# MCU.net
KiCad netlist of a schematic drawn in Altium Designer
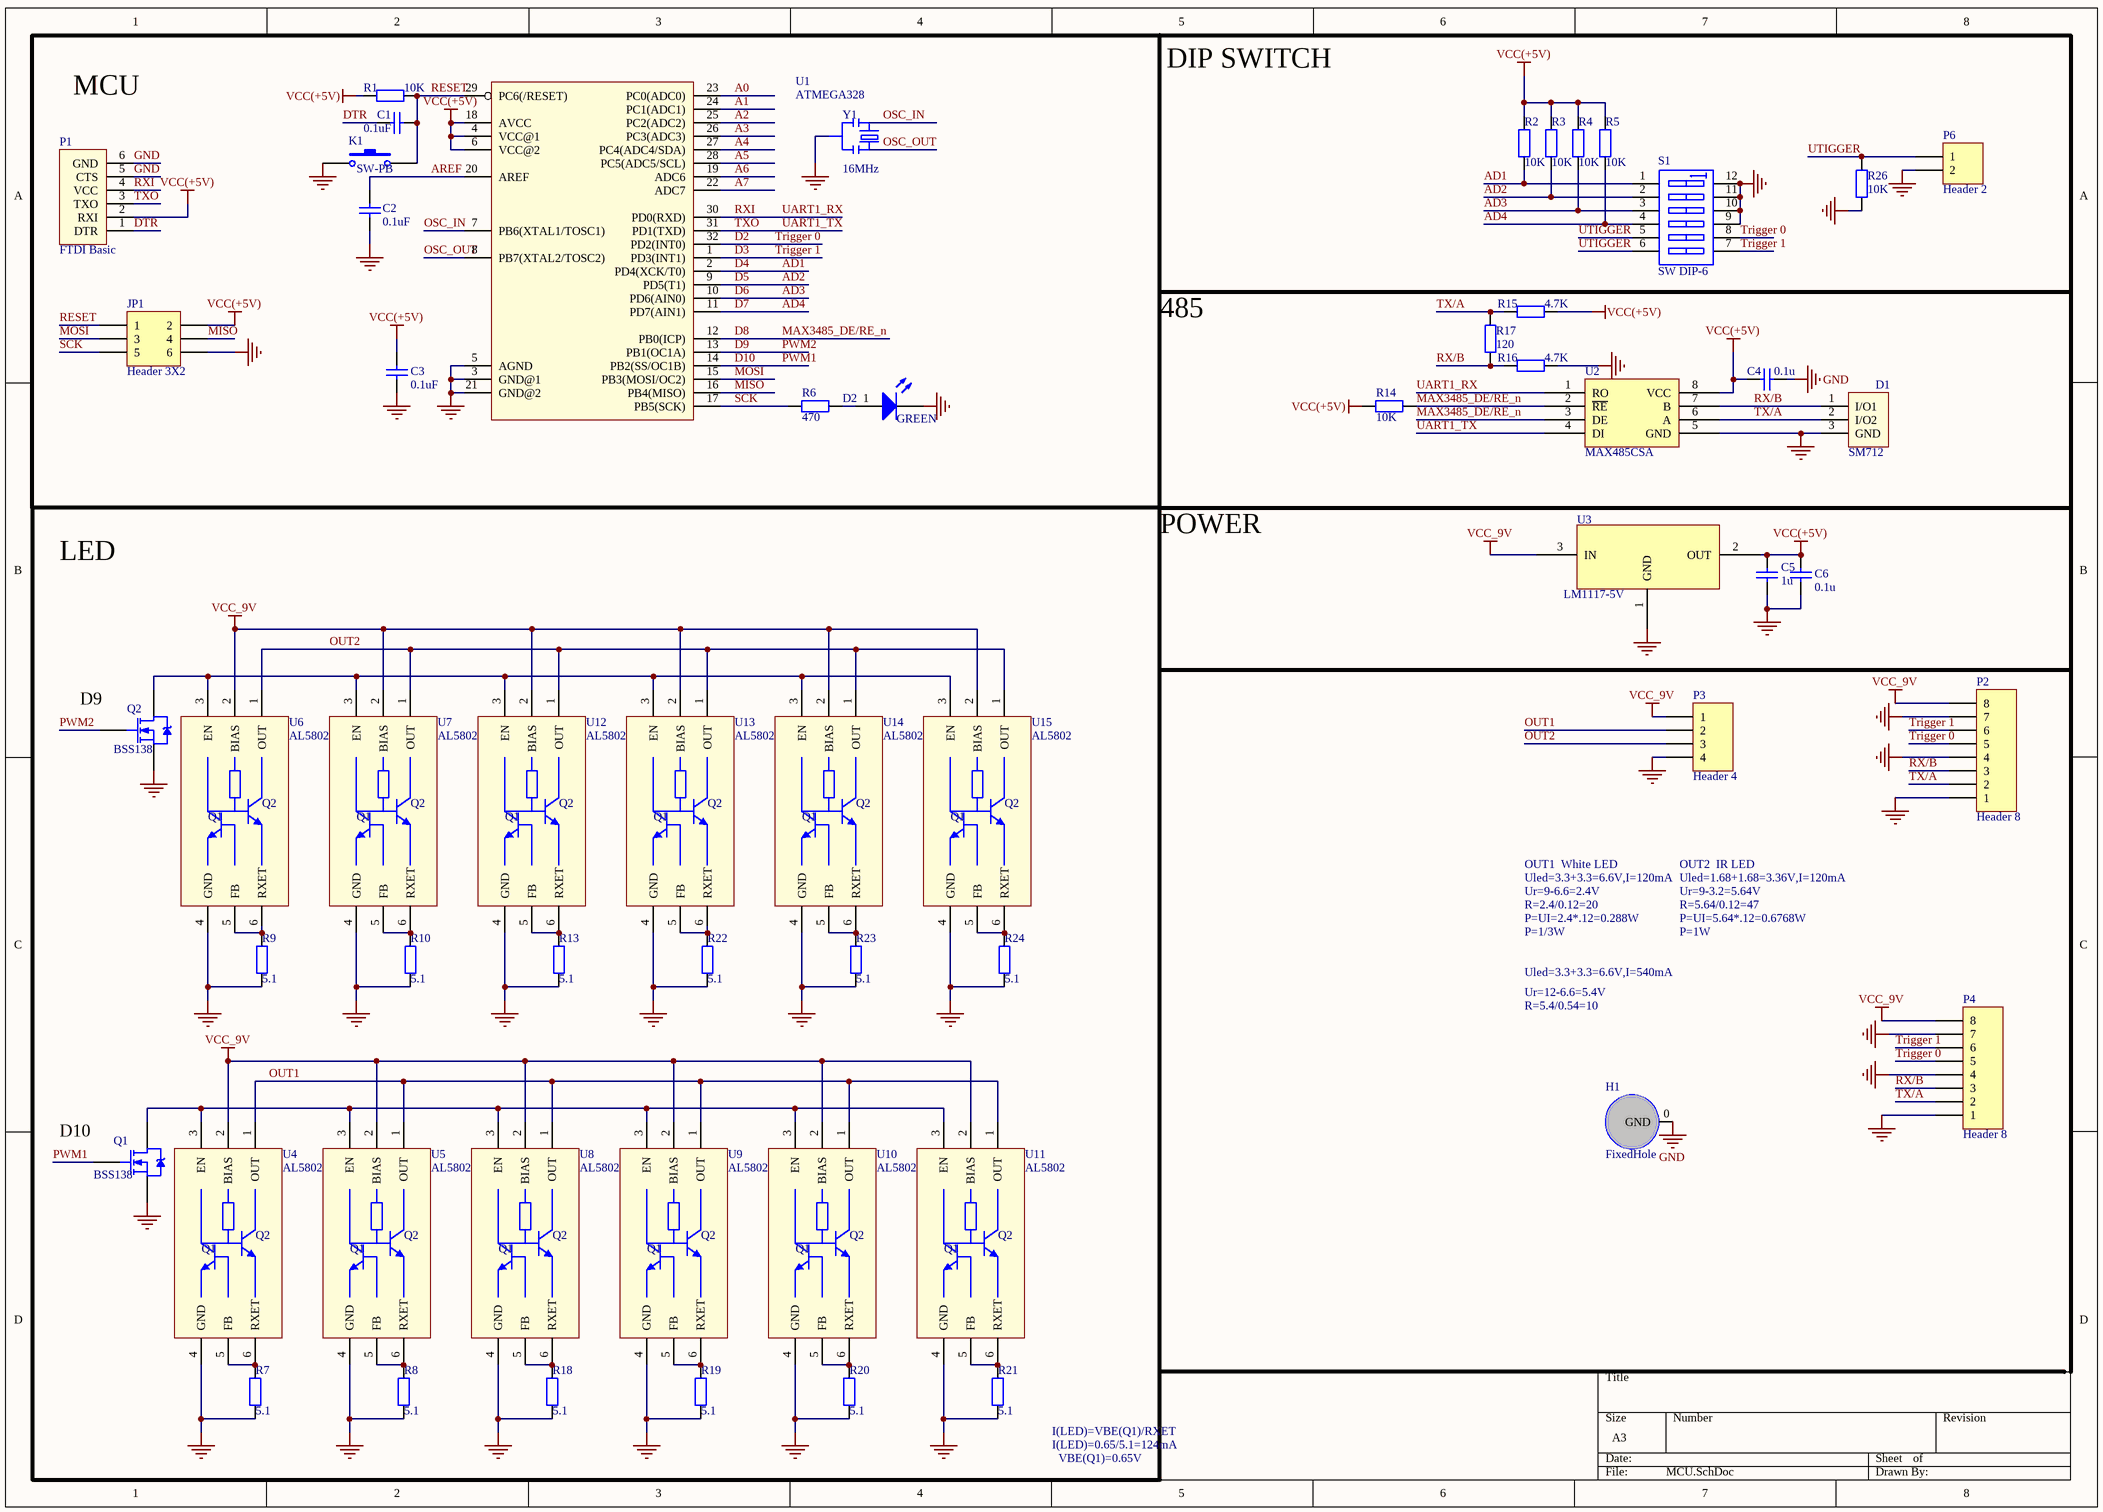
[diagram p0: MCU.SchDoc]

(export (version "E")
  (design (tool "Eeschema 10.0.6"))
  (components
    (comp (ref "C1")
      (value "0.1uF")
      (footprint "C0603")
      (description "Capacitor")
      (fields (field (name "IPARTNUMBER") "C100nF25V10%X7R") (field (name "VOLTAGE") "25V"))
      (libsource (lib "Schlib1") (part "CAP SMT C100nF25V10%X7R"))
    )
    (comp (ref "C2")
      (value "0.1uF")
      (footprint "C0603")
      (description "Capacitor")
      (fields (field (name "IPARTNUMBER") "C100nF25V10%X7R") (field (name "VOLTAGE") "25V"))
      (libsource (lib "Schlib1") (part "CAP SMT C100nF25V10%X7R"))
    )
    (comp (ref "C3")
      (value "0.1uF")
      (footprint "C0603")
      (description "Capacitor")
      (fields (field (name "IPARTNUMBER") "C100nF25V10%X7R") (field (name "VOLTAGE") "25V"))
      (libsource (lib "Schlib1") (part "CAP SMT C100nF25V10%X7R"))
    )
    (comp (ref "C4")
      (value "0.1u")
      (footprint "C0603")
      (description "Capacitor")
      (fields (field (name "PUBLISHER") "Altium Limited"))
      (libsource (lib "Miscellaneous Devices") (part "Cap"))
    )
    (comp (ref "C5")
      (value "1u")
      (footprint "C0603")
      (description "50V/8.2u/0805")
      (fields (field (name "PUBLISHER") "Altium Limited"))
      (libsource (lib "Miscellaneous Devices") (part "Cap"))
    )
    (comp (ref "C6")
      (value "0.1u")
      (footprint "C0603")
      (description "Capacitor")
      (fields (field (name "PUBLISHER") "Altium Limited"))
      (libsource (lib "WM360") (part "CAP0805"))
    )
    (comp (ref "D1")
      (value "SM712")
      (footprint "SOT23-3")
      (libsource (lib "STM32F4_CAM V2.0") (part "SM712"))
    )
    (comp (ref "D2")
      (value "GREEN")
      (footprint "LED0805")
      (description "Typical INFRARED GaAs LED")
      (fields (field (name "PUBLISHER") "Altium Limited"))
      (libsource (lib "DM642") (part "LED0"))
    )
    (comp (ref "H1") (value "FixedHole") (footprint "固定孔_1") (libsource (lib "ITMS-02调试电缆转接板") (part "固定孔")))
    (comp (ref "JP1")
      (value "Header 3X2")
      (footprint "MHDR1X6")
      (description "Header, 3-Pin, Dual row")
      (fields (field (name "PUBLISHER") "Altium Limited"))
      (libsource (lib "Miscellaneous Connectors") (part "Header 3X2"))
    )
    (comp (ref "K1")
      (value "SW-PB")
      (footprint "157SW")
      (description "Switch")
      (fields (field (name "PUBLISHER") "Altium Limited"))
      (libsource (lib "Miscellaneous Devices") (part "SW-PB"))
    )
    (comp (ref "P1")
      (value "FTDI Basic")
      (footprint "MHDR1X6")
      (libsource (lib "PCB_Project1") (part "ARDUINO_SERIAL_PROGRAMPTH"))
    )
    (comp (ref "P2")
      (value "Header 8")
      (footprint "SH_1.25MM*8")
      (description "Header, 8-Pin")
      (fields (field (name "PUBLISHER") "Altium Limited"))
      (libsource (lib "Miscellaneous Connectors") (part "Header 8"))
    )
    (comp (ref "P3")
      (value "Header 4")
      (footprint "SMT_1.25MM*4")
      (description "Header, 4-Pin")
      (fields (field (name "PUBLISHER") "Altium Limited"))
      (libsource (lib "Miscellaneous Connectors") (part "Header 4"))
    )
    (comp (ref "P4")
      (value "Header 8")
      (footprint "SH_1.25MM*8")
      (description "Header, 8-Pin")
      (fields (field (name "PUBLISHER") "Altium Limited"))
      (libsource (lib "Miscellaneous Connectors") (part "Header 8"))
    )
    (comp (ref "P6")
      (value "Header 2")
      (footprint "HDR1X2")
      (description "Header, 2-Pin")
      (fields (field (name "PUBLISHER") "Altium Limited"))
      (libsource (lib "Miscellaneous Connectors") (part "Header 2"))
    )
    (comp (ref "Q1")
      (value "BSS138")
      (footprint "SOT-23 (Standard)")
      (fields
        (field (name "MANUFACTURER") "Fairchild Semiconductor")
        (field (name "MANUFACTURER PART NUMBER") "BSS123")
      )
      (libsource (lib "Miscellaneous_Devices") (part "NMOS"))
    )
    (comp (ref "Q2")
      (value "BSS138")
      (footprint "SOT-23 (Standard)")
      (fields
        (field (name "MANUFACTURER") "Fairchild Semiconductor")
        (field (name "MANUFACTURER PART NUMBER") "BSS123")
      )
      (libsource (lib "Miscellaneous_Devices") (part "NMOS"))
    )
    (comp (ref "R1")
      (value "10K")
      (footprint "R0603")
      (description "Resistor")
      (libsource (lib "") (part "Res2_2"))
    )
    (comp (ref "R2")
      (value "10K")
      (footprint "R0603")
      (description "Resistor")
      (libsource (lib "") (part "Res2_1"))
    )
    (comp (ref "R3")
      (value "10K")
      (footprint "R0603")
      (description "Resistor")
      (libsource (lib "") (part "Res2_1"))
    )
    (comp (ref "R4")
      (value "10K")
      (footprint "R0603")
      (description "Resistor")
      (libsource (lib "") (part "Res2_1"))
    )
    (comp (ref "R5")
      (value "10K")
      (footprint "R0603")
      (description "Resistor")
      (libsource (lib "") (part "Res2_1"))
    )
    (comp (ref "R6")
      (value "470")
      (footprint "R0603")
      (description "Resistor")
      (libsource (lib "") (part "Res2_2"))
    )
    (comp (ref "R7")
      (value "5.1")
      (footprint "R0603")
      (description "Resistor")
      (libsource (lib "") (part "Res2_1"))
    )
    (comp (ref "R8")
      (value "5.1")
      (footprint "R0603")
      (description "Resistor")
      (libsource (lib "") (part "Res2_1"))
    )
    (comp (ref "R9")
      (value "5.1")
      (footprint "R0603")
      (description "Resistor")
      (libsource (lib "") (part "Res2_1"))
    )
    (comp (ref "R10")
      (value "5.1")
      (footprint "R0603")
      (description "Resistor")
      (libsource (lib "") (part "Res2_1"))
    )
    (comp (ref "R13")
      (value "5.1")
      (footprint "R0603")
      (description "Resistor")
      (libsource (lib "") (part "Res2_1"))
    )
    (comp (ref "R14")
      (value "10K")
      (footprint "R0603")
      (description "Resistor")
      (libsource (lib "DM642") (part "Res2"))
    )
    (comp (ref "R15")
      (value "4.7K")
      (footprint "R0603")
      (description "Resistor")
      (libsource (lib "DM642") (part "Res2"))
    )
    (comp (ref "R16")
      (value "4.7K")
      (footprint "R0603")
      (description "Resistor")
      (libsource (lib "DM642") (part "Res2"))
    )
    (comp (ref "R17")
      (value "120")
      (footprint "R0603")
      (description "Resistor")
      (libsource (lib "") (part "Res2_1"))
    )
    (comp (ref "R18")
      (value "5.1")
      (footprint "R0603")
      (description "Resistor")
      (libsource (lib "") (part "Res2_1"))
    )
    (comp (ref "R19")
      (value "5.1")
      (footprint "R0603")
      (description "Resistor")
      (libsource (lib "") (part "Res2_1"))
    )
    (comp (ref "R20")
      (value "5.1")
      (footprint "R0603")
      (description "Resistor")
      (libsource (lib "") (part "Res2_1"))
    )
    (comp (ref "R21")
      (value "5.1")
      (footprint "R0603")
      (description "Resistor")
      (libsource (lib "") (part "Res2_1"))
    )
    (comp (ref "R22")
      (value "5.1")
      (footprint "R0603")
      (description "Resistor")
      (libsource (lib "") (part "Res2_1"))
    )
    (comp (ref "R23")
      (value "5.1")
      (footprint "R0603")
      (description "Resistor")
      (libsource (lib "") (part "Res2_1"))
    )
    (comp (ref "R24")
      (value "5.1")
      (footprint "R0603")
      (description "Resistor")
      (libsource (lib "") (part "Res2_1"))
    )
    (comp (ref "R26")
      (value "10K")
      (footprint "R0603")
      (description "Resistor")
      (fields (field (name "PUBLISHER") "Altium Limited"))
      (libsource (lib "Miscellaneous Devices") (part "Res2"))
    )
    (comp (ref "S1")
      (value "SW DIP-6")
      (footprint "DIP_SW_6WAY_SMD")
      (description "DIP Switch, 6 Position, SPST")
      (fields (field (name "PUBLISHER") "Altium Limited"))
      (libsource (lib "Miscellaneous Devices") (part "SW DIP-6"))
    )
    (comp (ref "U1")
      (value "ATMEGA328")
      (footprint "TQFP32-08")
      (libsource (lib "PCB_Project1") (part "ATMEGA168"))
    )
    (comp (ref "U2")
      (value "MAX485CSA")
      (footprint "SOIC-8")
      (libsource (lib "STM32F4_CAM V1.2") (part "MAX3485CSA"))
    )
    (comp (ref "U3") (value "LM1117-5V") (footprint "SOT-223") (libsource (lib "rs232") (part "AMS1117")))
    (comp (ref "U4") (value "AL5802") (footprint "SOT26") (libsource (lib "LED") (part "AL5802")))
    (comp (ref "U5") (value "AL5802") (footprint "SOT26") (libsource (lib "LED") (part "AL5802")))
    (comp (ref "U6") (value "AL5802") (footprint "SOT26") (libsource (lib "LED") (part "AL5802")))
    (comp (ref "U7") (value "AL5802") (footprint "SOT26") (libsource (lib "LED") (part "AL5802")))
    (comp (ref "U8") (value "AL5802") (footprint "SOT26") (libsource (lib "LED") (part "AL5802")))
    (comp (ref "U9") (value "AL5802") (footprint "SOT26") (libsource (lib "LED") (part "AL5802")))
    (comp (ref "U10") (value "AL5802") (footprint "SOT26") (libsource (lib "LED") (part "AL5802")))
    (comp (ref "U11") (value "AL5802") (footprint "SOT26") (libsource (lib "LED") (part "AL5802")))
    (comp (ref "U12") (value "AL5802") (footprint "SOT26") (libsource (lib "LED") (part "AL5802")))
    (comp (ref "U13") (value "AL5802") (footprint "SOT26") (libsource (lib "LED") (part "AL5802")))
    (comp (ref "U14") (value "AL5802") (footprint "SOT26") (libsource (lib "LED") (part "AL5802")))
    (comp (ref "U15") (value "AL5802") (footprint "SOT26") (libsource (lib "LED") (part "AL5802")))
    (comp (ref "Y1")
      (value "16MHz")
      (footprint "RESONATOR-SMD")
      (libsource (lib "SparkFun") (part "RESONATORSMD"))
    )
  )
  (nets
    (net (code "1") (name "/A0") (class "Default")
      (node (ref "U1") (pin "23") (pinfunction "PC0(ADC0)_23") (pintype "passive"))
    )
    (net (code "2") (name "/A1") (class "Default")
      (node (ref "U1") (pin "24") (pinfunction "PC1(ADC1)_24") (pintype "passive"))
    )
    (net (code "3") (name "/A2") (class "Default")
      (node (ref "U1") (pin "25") (pinfunction "PC2(ADC2)_25") (pintype "passive"))
    )
    (net (code "4") (name "/A3") (class "Default")
      (node (ref "U1") (pin "26") (pinfunction "PC3(ADC3)_26") (pintype "passive"))
    )
    (net (code "5") (name "/A4") (class "Default")
      (node (ref "U1") (pin "27") (pinfunction "PC4(ADC4/SDA)_27") (pintype "passive"))
    )
    (net (code "6") (name "/A5") (class "Default")
      (node (ref "U1") (pin "28") (pinfunction "PC5(ADC5/SCL)_28") (pintype "passive"))
    )
    (net (code "7") (name "/A6") (class "Default")
      (node (ref "U1") (pin "19") (pinfunction "ADC6_19") (pintype "passive"))
    )
    (net (code "8") (name "/A7") (class "Default")
      (node (ref "U1") (pin "22") (pinfunction "ADC7_22") (pintype "passive"))
    )
    (net (code "9") (name "/AD1") (class "Default")
      (node (ref "R2") (pin "2") (pinfunction "2_2") (pintype "passive"))
      (node (ref "S1") (pin "1") (pinfunction "A1_1") (pintype "passive"))
      (node (ref "U1") (pin "2") (pinfunction "PD4(XCK/T0)_2") (pintype "passive"))
    )
    (net (code "10") (name "/AD2") (class "Default")
      (node (ref "R3") (pin "2") (pinfunction "2_2") (pintype "passive"))
      (node (ref "S1") (pin "2") (pinfunction "A2_2") (pintype "passive"))
      (node (ref "U1") (pin "9") (pinfunction "PD5(T1)_9") (pintype "passive"))
    )
    (net (code "11") (name "/AD3") (class "Default")
      (node (ref "R4") (pin "2") (pinfunction "2_2") (pintype "passive"))
      (node (ref "S1") (pin "3") (pinfunction "A3_3") (pintype "passive"))
      (node (ref "U1") (pin "10") (pinfunction "PD6(AIN0)_10") (pintype "passive"))
    )
    (net (code "12") (name "/AD4") (class "Default")
      (node (ref "R5") (pin "2") (pinfunction "2_2") (pintype "passive"))
      (node (ref "S1") (pin "4") (pinfunction "A4_4") (pintype "passive"))
      (node (ref "U1") (pin "11") (pinfunction "PD7(AIN1)_11") (pintype "passive"))
    )
    (net (code "13") (name "/AREF") (class "Default")
      (node (ref "C2") (pin "2") (pinfunction "2_2") (pintype "passive"))
      (node (ref "U1") (pin "20") (pinfunction "AREF_20") (pintype "passive"))
    )
    (net (code "14") (name "/D2") (class "Default")
      (node (ref "P2") (pin "5") (pinfunction "5_5") (pintype "passive"))
      (node (ref "P4") (pin "5") (pinfunction "5_5") (pintype "passive"))
      (node (ref "S1") (pin "8") (pinfunction "B5_8") (pintype "passive"))
      (node (ref "U1") (pin "32") (pinfunction "PD2(INT0)_32") (pintype "passive"))
    )
    (net (code "15") (name "/D3") (class "Default")
      (node (ref "P2") (pin "6") (pinfunction "6_6") (pintype "passive"))
      (node (ref "P4") (pin "6") (pinfunction "6_6") (pintype "passive"))
      (node (ref "S1") (pin "7") (pinfunction "B6_7") (pintype "passive"))
      (node (ref "U1") (pin "1") (pinfunction "PD3(INT1)_1") (pintype "passive"))
    )
    (net (code "16") (name "/D8") (class "Default")
      (node (ref "R14") (pin "1") (pinfunction "1_1") (pintype "passive"))
      (node (ref "U1") (pin "12") (pinfunction "PB0(ICP)_12") (pintype "passive"))
      (node (ref "U2") (pin "2") (pinfunction "~{RE}_2") (pintype "passive"))
      (node (ref "U2") (pin "3") (pinfunction "DE_3") (pintype "passive"))
    )
    (net (code "17") (name "/D9") (class "Default")
      (node (ref "Q2") (pin "G") (pinfunction "G_G") (pintype "passive"))
      (node (ref "U1") (pin "13") (pinfunction "PB1(OC1A)_13") (pintype "passive"))
    )
    (net (code "18") (name "/D10") (class "Default")
      (node (ref "Q1") (pin "G") (pinfunction "G_G") (pintype "passive"))
      (node (ref "U1") (pin "14") (pinfunction "PB2(SS/OC1B)_14") (pintype "passive"))
    )
    (net (code "19") (name "/DTR") (class "Default")
      (node (ref "C1") (pin "1") (pinfunction "1_1") (pintype "passive"))
      (node (ref "P1") (pin "1") (pinfunction "DTR_1") (pintype "passive"))
    )
    (net (code "20") (name "/MISO") (class "Default")
      (node (ref "JP1") (pin "4") (pinfunction "4_4") (pintype "passive"))
      (node (ref "U1") (pin "16") (pinfunction "PB4(MISO)_16") (pintype "passive"))
    )
    (net (code "21") (name "/MOSI") (class "Default")
      (node (ref "JP1") (pin "3") (pinfunction "3_3") (pintype "passive"))
      (node (ref "U1") (pin "15") (pinfunction "PB3(MOSI/OC2)_15") (pintype "passive"))
    )
    (net (code "22") (name "/OSC_IN") (class "Default")
      (node (ref "U1") (pin "7") (pinfunction "PB6(XTAL1/TOSC1)_7") (pintype "passive"))
      (node (ref "Y1") (pin "3") (pinfunction "3_3") (pintype "passive"))
    )
    (net (code "23") (name "/OSC_OUT") (class "Default")
      (node (ref "U1") (pin "8") (pinfunction "PB7(XTAL2/TOSC2)_8") (pintype "passive"))
      (node (ref "Y1") (pin "1") (pinfunction "1_1") (pintype "passive"))
    )
    (net (code "24") (name "/OUT1") (class "Default")
      (node (ref "P3") (pin "2") (pinfunction "2_2") (pintype "passive"))
      (node (ref "U10") (pin "1") (pinfunction "OUT_1") (pintype "passive"))
      (node (ref "U11") (pin "1") (pinfunction "OUT_1") (pintype "passive"))
      (node (ref "U4") (pin "1") (pinfunction "OUT_1") (pintype "passive"))
      (node (ref "U5") (pin "1") (pinfunction "OUT_1") (pintype "passive"))
      (node (ref "U8") (pin "1") (pinfunction "OUT_1") (pintype "passive"))
      (node (ref "U9") (pin "1") (pinfunction "OUT_1") (pintype "passive"))
    )
    (net (code "25") (name "/OUT2") (class "Default")
      (node (ref "P3") (pin "3") (pinfunction "3_3") (pintype "passive"))
      (node (ref "U12") (pin "1") (pinfunction "OUT_1") (pintype "passive"))
      (node (ref "U13") (pin "1") (pinfunction "OUT_1") (pintype "passive"))
      (node (ref "U14") (pin "1") (pinfunction "OUT_1") (pintype "passive"))
      (node (ref "U15") (pin "1") (pinfunction "OUT_1") (pintype "passive"))
      (node (ref "U6") (pin "1") (pinfunction "OUT_1") (pintype "passive"))
      (node (ref "U7") (pin "1") (pinfunction "OUT_1") (pintype "passive"))
    )
    (net (code "26") (name "/RESET") (class "Default")
      (node (ref "C1") (pin "2") (pinfunction "2_2") (pintype "passive"))
      (node (ref "JP1") (pin "1") (pinfunction "1_1") (pintype "passive"))
      (node (ref "K1") (pin "2") (pinfunction "2_2") (pintype "passive"))
      (node (ref "R1") (pin "2") (pinfunction "2_2") (pintype "passive"))
      (node (ref "U1") (pin "29") (pinfunction "PC6(/RESET)_29") (pintype "passive"))
    )
    (net (code "27") (name "/RXI") (class "Default")
      (node (ref "P1") (pin "4") (pinfunction "VCC_4") (pintype "passive"))
      (node (ref "U1") (pin "30") (pinfunction "PD0(RXD)_30") (pintype "passive"))
      (node (ref "U2") (pin "1") (pinfunction "RO_1") (pintype "passive"))
    )
    (net (code "28") (name "/RX{slash}B") (class "Default")
      (node (ref "D1") (pin "1") (pinfunction "I/O1_1") (pintype "passive"))
      (node (ref "P2") (pin "3") (pinfunction "3_3") (pintype "passive"))
      (node (ref "P4") (pin "3") (pinfunction "3_3") (pintype "passive"))
      (node (ref "R16") (pin "2") (pinfunction "2_2") (pintype "passive"))
      (node (ref "R17") (pin "2") (pinfunction "2_2") (pintype "passive"))
      (node (ref "U2") (pin "7") (pinfunction "B_7") (pintype "passive"))
    )
    (net (code "29") (name "/SCK") (class "Default")
      (node (ref "JP1") (pin "5") (pinfunction "5_5") (pintype "passive"))
      (node (ref "R6") (pin "1") (pinfunction "1_1") (pintype "passive"))
      (node (ref "U1") (pin "17") (pinfunction "PB5(SCK)_17") (pintype "passive"))
    )
    (net (code "30") (name "/TXO") (class "Default")
      (node (ref "P1") (pin "3") (pinfunction "TXO_3") (pintype "passive"))
      (node (ref "U1") (pin "31") (pinfunction "PD1(TXD)_31") (pintype "passive"))
      (node (ref "U2") (pin "4") (pinfunction "DI_4") (pintype "passive"))
    )
    (net (code "31") (name "/TX{slash}A") (class "Default")
      (node (ref "D1") (pin "2") (pinfunction "I/O2_2") (pintype "passive"))
      (node (ref "P2") (pin "2") (pinfunction "2_2") (pintype "passive"))
      (node (ref "P4") (pin "2") (pinfunction "2_2") (pintype "passive"))
      (node (ref "R15") (pin "2") (pinfunction "2_2") (pintype "passive"))
      (node (ref "R17") (pin "1") (pinfunction "1_1") (pintype "passive"))
      (node (ref "U2") (pin "6") (pinfunction "A_6") (pintype "passive"))
    )
    (net (code "32") (name "/UTIGGER") (class "Default")
      (node (ref "P6") (pin "1") (pinfunction "1_1") (pintype "passive"))
      (node (ref "R26") (pin "2") (pinfunction "2_2") (pintype "passive"))
      (node (ref "S1") (pin "5") (pinfunction "A5_5") (pintype "passive"))
      (node (ref "S1") (pin "6") (pinfunction "A6_6") (pintype "passive"))
    )
    (net (code "33") (name "GND") (class "Default")
      (node (ref "C2") (pin "1") (pinfunction "1_1") (pintype "passive"))
      (node (ref "C3") (pin "2") (pinfunction "2_2") (pintype "passive"))
      (node (ref "C4") (pin "1") (pinfunction "1_1") (pintype "passive"))
      (node (ref "C5") (pin "1") (pinfunction "1_1") (pintype "passive"))
      (node (ref "C6") (pin "2") (pinfunction "2_2") (pintype "passive"))
      (node (ref "D1") (pin "3") (pinfunction "GND_3") (pintype "passive"))
      (node (ref "D2") (pin "2") (pinfunction "K_2") (pintype "passive"))
      (node (ref "H1") (pin "0") (pinfunction "GND_0") (pintype "passive"))
      (node (ref "JP1") (pin "6") (pinfunction "6_6") (pintype "passive"))
      (node (ref "K1") (pin "1") (pinfunction "1_1") (pintype "passive"))
      (node (ref "P1") (pin "5") (pinfunction "CTS_5") (pintype "passive"))
      (node (ref "P1") (pin "6") (pinfunction "GND_6") (pintype "passive"))
      (node (ref "P2") (pin "1") (pinfunction "1_1") (pintype "passive"))
      (node (ref "P2") (pin "4") (pinfunction "4_4") (pintype "passive"))
      (node (ref "P2") (pin "7") (pinfunction "7_7") (pintype "passive"))
      (node (ref "P3") (pin "4") (pinfunction "4_4") (pintype "passive"))
      (node (ref "P4") (pin "1") (pinfunction "1_1") (pintype "passive"))
      (node (ref "P4") (pin "4") (pinfunction "4_4") (pintype "passive"))
      (node (ref "P4") (pin "7") (pinfunction "7_7") (pintype "passive"))
      (node (ref "P6") (pin "2") (pinfunction "2_2") (pintype "passive"))
      (node (ref "Q1") (pin "S") (pinfunction "S_S") (pintype "passive"))
      (node (ref "Q2") (pin "S") (pinfunction "S_S") (pintype "passive"))
      (node (ref "R10") (pin "2") (pinfunction "2_2") (pintype "passive"))
      (node (ref "R13") (pin "2") (pinfunction "2_2") (pintype "passive"))
      (node (ref "R16") (pin "1") (pinfunction "1_1") (pintype "passive"))
      (node (ref "R18") (pin "2") (pinfunction "2_2") (pintype "passive"))
      (node (ref "R19") (pin "2") (pinfunction "2_2") (pintype "passive"))
      (node (ref "R20") (pin "2") (pinfunction "2_2") (pintype "passive"))
      (node (ref "R21") (pin "2") (pinfunction "2_2") (pintype "passive"))
      (node (ref "R22") (pin "2") (pinfunction "2_2") (pintype "passive"))
      (node (ref "R23") (pin "2") (pinfunction "2_2") (pintype "passive"))
      (node (ref "R24") (pin "2") (pinfunction "2_2") (pintype "passive"))
      (node (ref "R26") (pin "1") (pinfunction "1_1") (pintype "passive"))
      (node (ref "R7") (pin "2") (pinfunction "2_2") (pintype "passive"))
      (node (ref "R8") (pin "2") (pinfunction "2_2") (pintype "passive"))
      (node (ref "R9") (pin "2") (pinfunction "2_2") (pintype "passive"))
      (node (ref "S1") (pin "10") (pinfunction "B3_10") (pintype "passive"))
      (node (ref "S1") (pin "11") (pinfunction "B2_11") (pintype "passive"))
      (node (ref "S1") (pin "12") (pinfunction "B1_12") (pintype "passive"))
      (node (ref "S1") (pin "9") (pinfunction "B4_9") (pintype "passive"))
      (node (ref "U1") (pin "21") (pinfunction "GND@2_21") (pintype "passive"))
      (node (ref "U1") (pin "3") (pinfunction "GND@1_3") (pintype "passive"))
      (node (ref "U1") (pin "5") (pinfunction "AGND_5") (pintype "passive"))
      (node (ref "U10") (pin "4") (pinfunction "GND_4") (pintype "passive"))
      (node (ref "U11") (pin "4") (pinfunction "GND_4") (pintype "passive"))
      (node (ref "U12") (pin "4") (pinfunction "GND_4") (pintype "passive"))
      (node (ref "U13") (pin "4") (pinfunction "GND_4") (pintype "passive"))
      (node (ref "U14") (pin "4") (pinfunction "GND_4") (pintype "passive"))
      (node (ref "U15") (pin "4") (pinfunction "GND_4") (pintype "passive"))
      (node (ref "U2") (pin "5") (pinfunction "GND_5") (pintype "passive"))
      (node (ref "U3") (pin "1") (pinfunction "GND_1") (pintype "passive"))
      (node (ref "U4") (pin "4") (pinfunction "GND_4") (pintype "passive"))
      (node (ref "U5") (pin "4") (pinfunction "GND_4") (pintype "passive"))
      (node (ref "U6") (pin "4") (pinfunction "GND_4") (pintype "passive"))
      (node (ref "U7") (pin "4") (pinfunction "GND_4") (pintype "passive"))
      (node (ref "U8") (pin "4") (pinfunction "GND_4") (pintype "passive"))
      (node (ref "U9") (pin "4") (pinfunction "GND_4") (pintype "passive"))
      (node (ref "Y1") (pin "2") (pinfunction "2_2") (pintype "passive"))
    )
    (net (code "34") (name "Net-(D2-A)") (class "Default")
      (node (ref "D2") (pin "1") (pinfunction "A_1") (pintype "passive"))
      (node (ref "R6") (pin "2") (pinfunction "2_2") (pintype "passive"))
    )
    (net (code "35") (name "Net-(U4-FB)") (class "Default")
      (node (ref "R7") (pin "1") (pinfunction "1_1") (pintype "passive"))
      (node (ref "U4") (pin "5") (pinfunction "FB_5") (pintype "passive"))
      (node (ref "U4") (pin "6") (pinfunction "RXET_6") (pintype "passive"))
    )
    (net (code "36") (name "Net-(U5-FB)") (class "Default")
      (node (ref "R8") (pin "1") (pinfunction "1_1") (pintype "passive"))
      (node (ref "U5") (pin "5") (pinfunction "FB_5") (pintype "passive"))
      (node (ref "U5") (pin "6") (pinfunction "RXET_6") (pintype "passive"))
    )
    (net (code "37") (name "Net-(U6-FB)") (class "Default")
      (node (ref "R9") (pin "1") (pinfunction "1_1") (pintype "passive"))
      (node (ref "U6") (pin "5") (pinfunction "FB_5") (pintype "passive"))
      (node (ref "U6") (pin "6") (pinfunction "RXET_6") (pintype "passive"))
    )
    (net (code "38") (name "Net-(U7-FB)") (class "Default")
      (node (ref "R10") (pin "1") (pinfunction "1_1") (pintype "passive"))
      (node (ref "U7") (pin "5") (pinfunction "FB_5") (pintype "passive"))
      (node (ref "U7") (pin "6") (pinfunction "RXET_6") (pintype "passive"))
    )
    (net (code "39") (name "Net-(U8-FB)") (class "Default")
      (node (ref "R18") (pin "1") (pinfunction "1_1") (pintype "passive"))
      (node (ref "U8") (pin "5") (pinfunction "FB_5") (pintype "passive"))
      (node (ref "U8") (pin "6") (pinfunction "RXET_6") (pintype "passive"))
    )
    (net (code "40") (name "Net-(U9-FB)") (class "Default")
      (node (ref "R19") (pin "1") (pinfunction "1_1") (pintype "passive"))
      (node (ref "U9") (pin "5") (pinfunction "FB_5") (pintype "passive"))
      (node (ref "U9") (pin "6") (pinfunction "RXET_6") (pintype "passive"))
    )
    (net (code "41") (name "Net-(U10-EN)") (class "Default")
      (node (ref "Q1") (pin "D") (pinfunction "D_D") (pintype "passive"))
      (node (ref "U10") (pin "3") (pinfunction "EN_3") (pintype "passive"))
      (node (ref "U11") (pin "3") (pinfunction "EN_3") (pintype "passive"))
      (node (ref "U4") (pin "3") (pinfunction "EN_3") (pintype "passive"))
      (node (ref "U5") (pin "3") (pinfunction "EN_3") (pintype "passive"))
      (node (ref "U8") (pin "3") (pinfunction "EN_3") (pintype "passive"))
      (node (ref "U9") (pin "3") (pinfunction "EN_3") (pintype "passive"))
    )
    (net (code "42") (name "Net-(U10-FB)") (class "Default")
      (node (ref "R20") (pin "1") (pinfunction "1_1") (pintype "passive"))
      (node (ref "U10") (pin "5") (pinfunction "FB_5") (pintype "passive"))
      (node (ref "U10") (pin "6") (pinfunction "RXET_6") (pintype "passive"))
    )
    (net (code "43") (name "Net-(U11-FB)") (class "Default")
      (node (ref "R21") (pin "1") (pinfunction "1_1") (pintype "passive"))
      (node (ref "U11") (pin "5") (pinfunction "FB_5") (pintype "passive"))
      (node (ref "U11") (pin "6") (pinfunction "RXET_6") (pintype "passive"))
    )
    (net (code "44") (name "Net-(U12-EN)") (class "Default")
      (node (ref "Q2") (pin "D") (pinfunction "D_D") (pintype "passive"))
      (node (ref "U12") (pin "3") (pinfunction "EN_3") (pintype "passive"))
      (node (ref "U13") (pin "3") (pinfunction "EN_3") (pintype "passive"))
      (node (ref "U14") (pin "3") (pinfunction "EN_3") (pintype "passive"))
      (node (ref "U15") (pin "3") (pinfunction "EN_3") (pintype "passive"))
      (node (ref "U6") (pin "3") (pinfunction "EN_3") (pintype "passive"))
      (node (ref "U7") (pin "3") (pinfunction "EN_3") (pintype "passive"))
    )
    (net (code "45") (name "Net-(U12-FB)") (class "Default")
      (node (ref "R13") (pin "1") (pinfunction "1_1") (pintype "passive"))
      (node (ref "U12") (pin "5") (pinfunction "FB_5") (pintype "passive"))
      (node (ref "U12") (pin "6") (pinfunction "RXET_6") (pintype "passive"))
    )
    (net (code "46") (name "Net-(U13-FB)") (class "Default")
      (node (ref "R22") (pin "1") (pinfunction "1_1") (pintype "passive"))
      (node (ref "U13") (pin "5") (pinfunction "FB_5") (pintype "passive"))
      (node (ref "U13") (pin "6") (pinfunction "RXET_6") (pintype "passive"))
    )
    (net (code "47") (name "Net-(U14-FB)") (class "Default")
      (node (ref "R23") (pin "1") (pinfunction "1_1") (pintype "passive"))
      (node (ref "U14") (pin "5") (pinfunction "FB_5") (pintype "passive"))
      (node (ref "U14") (pin "6") (pinfunction "RXET_6") (pintype "passive"))
    )
    (net (code "48") (name "Net-(U15-FB)") (class "Default")
      (node (ref "R24") (pin "1") (pinfunction "1_1") (pintype "passive"))
      (node (ref "U15") (pin "5") (pinfunction "FB_5") (pintype "passive"))
      (node (ref "U15") (pin "6") (pinfunction "RXET_6") (pintype "passive"))
    )
    (net (code "49") (name "VCC(+5V)") (class "Default")
      (node (ref "C3") (pin "1") (pinfunction "1_1") (pintype "passive"))
      (node (ref "C4") (pin "2") (pinfunction "2_2") (pintype "passive"))
      (node (ref "C5") (pin "2") (pinfunction "2_2") (pintype "passive"))
      (node (ref "C6") (pin "1") (pinfunction "1_1") (pintype "passive"))
      (node (ref "JP1") (pin "2") (pinfunction "2_2") (pintype "passive"))
      (node (ref "P1") (pin "2") (pinfunction "RXI_2") (pintype "passive"))
      (node (ref "R1") (pin "1") (pinfunction "1_1") (pintype "passive"))
      (node (ref "R14") (pin "2") (pinfunction "2_2") (pintype "passive"))
      (node (ref "R15") (pin "1") (pinfunction "1_1") (pintype "passive"))
      (node (ref "R2") (pin "1") (pinfunction "1_1") (pintype "passive"))
      (node (ref "R3") (pin "1") (pinfunction "1_1") (pintype "passive"))
      (node (ref "R4") (pin "1") (pinfunction "1_1") (pintype "passive"))
      (node (ref "R5") (pin "1") (pinfunction "1_1") (pintype "passive"))
      (node (ref "U1") (pin "18") (pinfunction "AVCC_18") (pintype "passive"))
      (node (ref "U1") (pin "4") (pinfunction "VCC@1_4") (pintype "passive"))
      (node (ref "U1") (pin "6") (pinfunction "VCC@2_6") (pintype "passive"))
      (node (ref "U2") (pin "8") (pinfunction "VCC_8") (pintype "passive"))
      (node (ref "U3") (pin "2") (pinfunction "OUT_2") (pintype "passive"))
    )
    (net (code "50") (name "VCC_9V") (class "Default")
      (node (ref "P2") (pin "8") (pinfunction "8_8") (pintype "passive"))
      (node (ref "P3") (pin "1") (pinfunction "1_1") (pintype "passive"))
      (node (ref "P4") (pin "8") (pinfunction "8_8") (pintype "passive"))
      (node (ref "U10") (pin "2") (pinfunction "BIAS_2") (pintype "passive"))
      (node (ref "U11") (pin "2") (pinfunction "BIAS_2") (pintype "passive"))
      (node (ref "U12") (pin "2") (pinfunction "BIAS_2") (pintype "passive"))
      (node (ref "U13") (pin "2") (pinfunction "BIAS_2") (pintype "passive"))
      (node (ref "U14") (pin "2") (pinfunction "BIAS_2") (pintype "passive"))
      (node (ref "U15") (pin "2") (pinfunction "BIAS_2") (pintype "passive"))
      (node (ref "U3") (pin "3") (pinfunction "IN_3") (pintype "passive"))
      (node (ref "U4") (pin "2") (pinfunction "BIAS_2") (pintype "passive"))
      (node (ref "U5") (pin "2") (pinfunction "BIAS_2") (pintype "passive"))
      (node (ref "U6") (pin "2") (pinfunction "BIAS_2") (pintype "passive"))
      (node (ref "U7") (pin "2") (pinfunction "BIAS_2") (pintype "passive"))
      (node (ref "U8") (pin "2") (pinfunction "BIAS_2") (pintype "passive"))
      (node (ref "U9") (pin "2") (pinfunction "BIAS_2") (pintype "passive"))
    )
  )
)
